# HDMI.net
KiCad netlist of a schematic drawn in Altium Designer
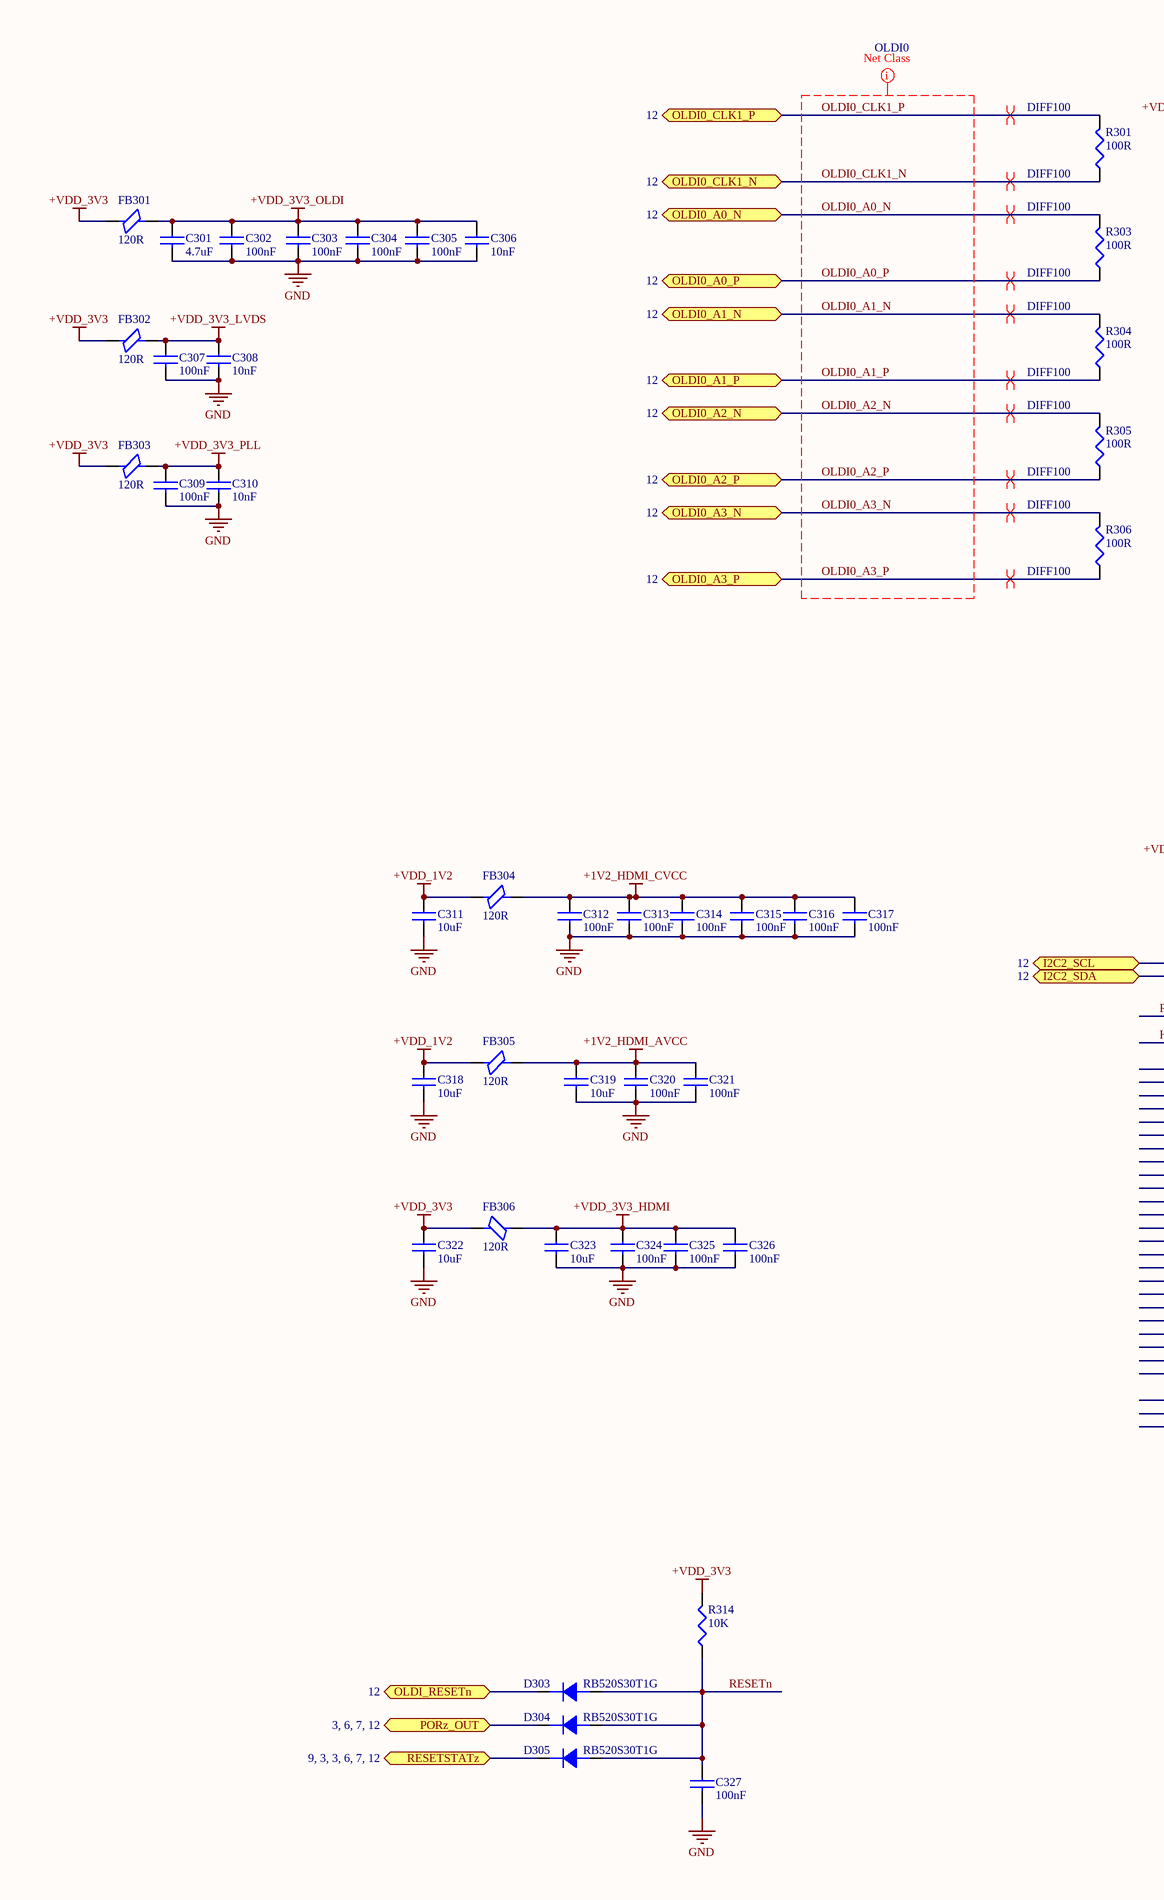
[diagram p0: HDMI.SchDoc, left]
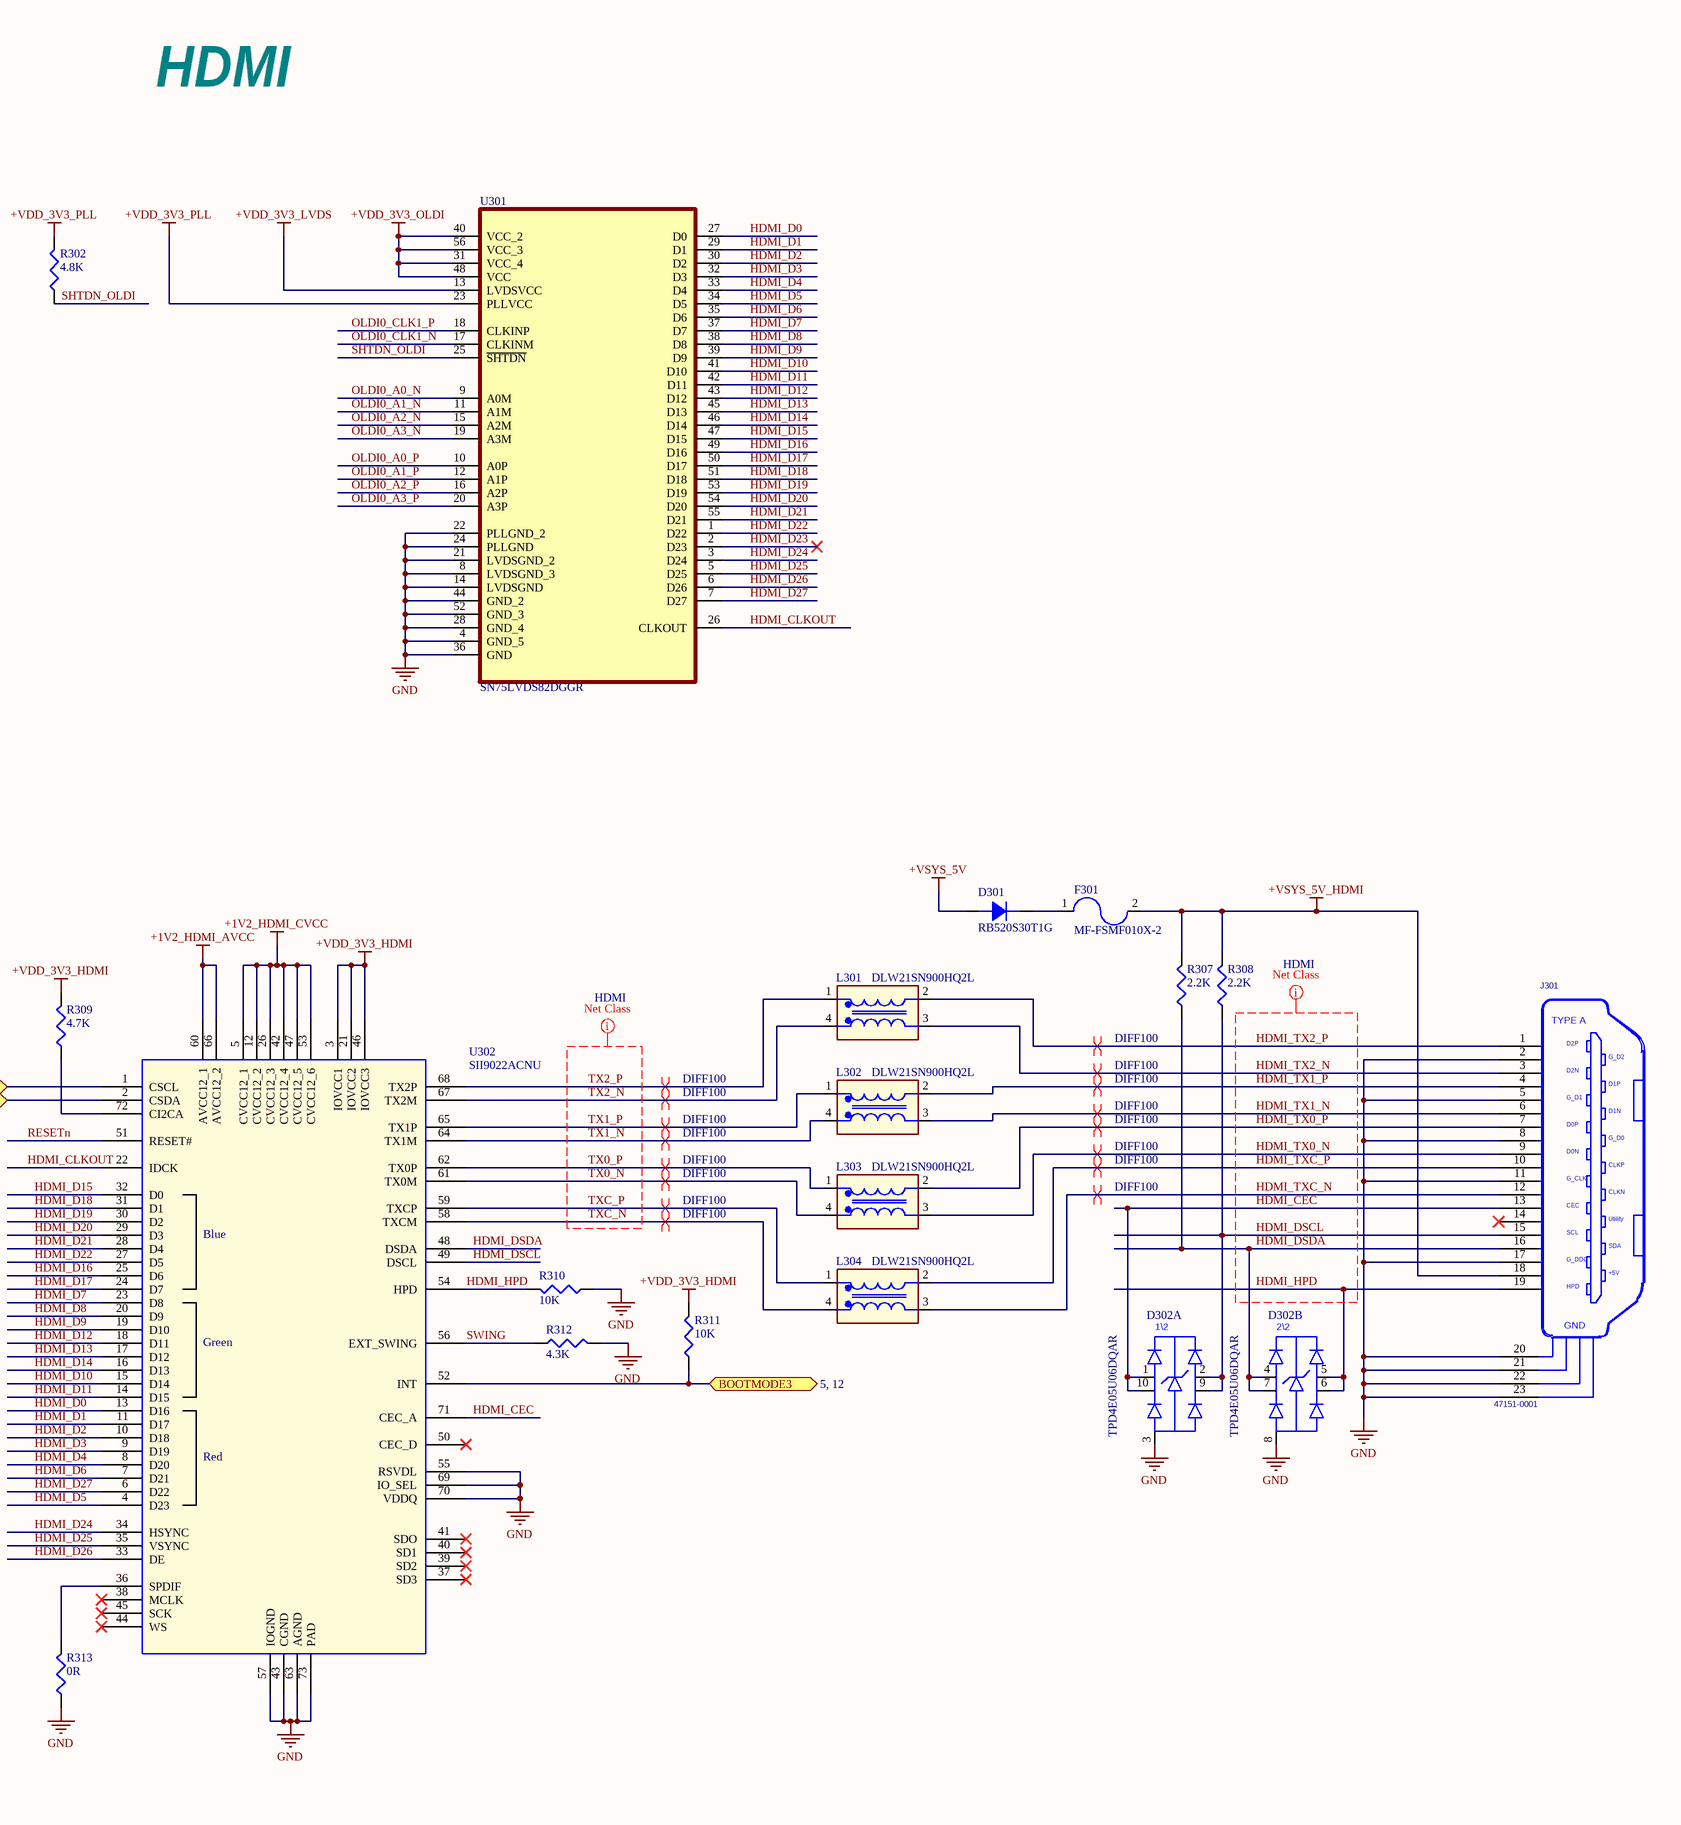
[diagram p1: HDMI.SchDoc, right]

(export (version "E")
  (design (tool "Eeschema 10.0.6"))
  (components
    (comp (ref "C301")
      (value "4.7uF")
      (footprint "C0402")
      (description "Multilayer Ceramic Capacitor, 4.7 uF, 6.3V, ± 10%, X5R, 0402 [1005 Metric]")
      (fields
        (field (name "MANUFACTURER") "Yageo")
        (field (name "MANUFACTURER PART NUMBER") "CC0402MRX5R5BB475")
      )
      (libsource (lib "Schlib SOM AM625") (part "CC0402MRX5R5BB475"))
    )
    (comp (ref "C302")
      (value "100nF")
      (footprint "C0603")
      (description "Multilayer Ceramic Capacitor, 0.1 uF, 25 V, ± 10%, X7R, 0603 [1608 Metric]")
      (fields
        (field (name "MANUFACTURER") "TDK")
        (field (name "MANUFACTURER PART NUMBER") "C1608X7R1E104K080AA")
      )
      (libsource (lib "Schlib SOM AM625") (part "C1608X7R1E104K080AA"))
    )
    (comp (ref "C303")
      (value "100nF")
      (footprint "C0603")
      (description "Multilayer Ceramic Capacitor, 0.1 uF, 25 V, ± 10%, X7R, 0603 [1608 Metric]")
      (fields
        (field (name "MANUFACTURER") "TDK")
        (field (name "MANUFACTURER PART NUMBER") "C1608X7R1E104K080AA")
      )
      (libsource (lib "Schlib SOM AM625") (part "C1608X7R1E104K080AA"))
    )
    (comp (ref "C304")
      (value "100nF")
      (footprint "C0603")
      (description "Multilayer Ceramic Capacitor, 0.1 uF, 25 V, ± 10%, X7R, 0603 [1608 Metric]")
      (fields
        (field (name "MANUFACTURER") "TDK")
        (field (name "MANUFACTURER PART NUMBER") "C1608X7R1E104K080AA")
      )
      (libsource (lib "Schlib SOM AM625") (part "C1608X7R1E104K080AA"))
    )
    (comp (ref "C305")
      (value "100nF")
      (footprint "C0603")
      (description "Multilayer Ceramic Capacitor, 0.1 uF, 25 V, ± 10%, X7R, 0603 [1608 Metric]")
      (fields
        (field (name "MANUFACTURER") "TDK")
        (field (name "MANUFACTURER PART NUMBER") "C1608X7R1E104K080AA")
      )
      (libsource (lib "Schlib SOM AM625") (part "C1608X7R1E104K080AA"))
    )
    (comp (ref "C306")
      (value "10nF")
      (footprint "C0402")
      (description "ESD SMD Comm X7R 0402 (1005Metric) ceramic capacitor 0.039Lx0.020W 1.00mmx0.50mm X7R ±10% 10000pF")
      (fields
        (field (name "MANUFACTURER") "KEMET")
        (field (name "MANUFACTURER PART NUMBER") "C0402C103K4REC7411")
      )
      (libsource (lib "Schlib SOM AM625") (part "C0402C103K4REC7411"))
    )
    (comp (ref "C307")
      (value "100nF")
      (footprint "C0603")
      (description "Multilayer Ceramic Capacitor, 0.1 uF, 25 V, ± 10%, X7R, 0603 [1608 Metric]")
      (fields
        (field (name "MANUFACTURER") "TDK")
        (field (name "MANUFACTURER PART NUMBER") "C1608X7R1E104K080AA")
      )
      (libsource (lib "Schlib SOM AM625") (part "C1608X7R1E104K080AA"))
    )
    (comp (ref "C308")
      (value "10nF")
      (footprint "C0402")
      (description "ESD SMD Comm X7R 0402 (1005Metric) ceramic capacitor 0.039Lx0.020W 1.00mmx0.50mm X7R ±10% 10000pF")
      (fields
        (field (name "MANUFACTURER") "KEMET")
        (field (name "MANUFACTURER PART NUMBER") "C0402C103K4REC7411")
      )
      (libsource (lib "Schlib SOM AM625") (part "C0402C103K4REC7411"))
    )
    (comp (ref "C309")
      (value "100nF")
      (footprint "C0603")
      (description "Multilayer Ceramic Capacitor, 0.1 uF, 25 V, ± 10%, X7R, 0603 [1608 Metric]")
      (fields
        (field (name "MANUFACTURER") "TDK")
        (field (name "MANUFACTURER PART NUMBER") "C1608X7R1E104K080AA")
      )
      (libsource (lib "Schlib SOM AM625") (part "C1608X7R1E104K080AA"))
    )
    (comp (ref "C310")
      (value "10nF")
      (footprint "C0402")
      (description "ESD SMD Comm X7R 0402 (1005Metric) ceramic capacitor 0.039Lx0.020W 1.00mmx0.50mm X7R ±10% 10000pF")
      (fields
        (field (name "MANUFACTURER") "KEMET")
        (field (name "MANUFACTURER PART NUMBER") "C0402C103K4REC7411")
      )
      (libsource (lib "Schlib SOM AM625") (part "C0402C103K4REC7411"))
    )
    (comp (ref "C311")
      (value "10uF")
      (footprint "C0603")
      (description "Multilayer Ceramic Capacitor, 10 uF, 10 V, ± 10%, X5R, 0603 [1608 Metric]")
      (fields
        (field (name "MANUFACTURER") "TDK")
        (field (name "MANUFACTURER PART NUMBER") "C1608X5R1A106K080AC")
      )
      (libsource (lib "Schlib SOM AM625") (part "C1608X5R1A106K080AC"))
    )
    (comp (ref "C312")
      (value "100nF")
      (footprint "C0201")
      (description "Multilayer Ceramic Capacitor, 0.1 uF, 16 V, ± 10%, X5R, 0201 [0603 Metric]")
      (fields
        (field (name "MANUFACTURER") "Yageo")
        (field (name "MANUFACTURER PART NUMBER") "CC0201KRX5R6BB104")
      )
      (libsource (lib "Schlib SOM AM625") (part "CC0201KRX5R6BB104"))
    )
    (comp (ref "C313")
      (value "100nF")
      (footprint "C0201")
      (description "Multilayer Ceramic Capacitor, 0.1 uF, 16 V, ± 10%, X5R, 0201 [0603 Metric]")
      (fields
        (field (name "MANUFACTURER") "Yageo")
        (field (name "MANUFACTURER PART NUMBER") "CC0201KRX5R6BB104")
      )
      (libsource (lib "Schlib SOM AM625") (part "CC0201KRX5R6BB104"))
    )
    (comp (ref "C314")
      (value "100nF")
      (footprint "C0201")
      (description "Multilayer Ceramic Capacitor, 0.1 uF, 16 V, ± 10%, X5R, 0201 [0603 Metric]")
      (fields
        (field (name "MANUFACTURER") "Yageo")
        (field (name "MANUFACTURER PART NUMBER") "CC0201KRX5R6BB104")
      )
      (libsource (lib "Schlib SOM AM625") (part "CC0201KRX5R6BB104"))
    )
    (comp (ref "C315")
      (value "100nF")
      (footprint "C0201")
      (description "Multilayer Ceramic Capacitor, 0.1 uF, 16 V, ± 10%, X5R, 0201 [0603 Metric]")
      (fields
        (field (name "MANUFACTURER") "Yageo")
        (field (name "MANUFACTURER PART NUMBER") "CC0201KRX5R6BB104")
      )
      (libsource (lib "Schlib SOM AM625") (part "CC0201KRX5R6BB104"))
    )
    (comp (ref "C316")
      (value "100nF")
      (footprint "C0201")
      (description "Multilayer Ceramic Capacitor, 0.1 uF, 16 V, ± 10%, X5R, 0201 [0603 Metric]")
      (fields
        (field (name "MANUFACTURER") "Yageo")
        (field (name "MANUFACTURER PART NUMBER") "CC0201KRX5R6BB104")
      )
      (libsource (lib "Schlib SOM AM625") (part "CC0201KRX5R6BB104"))
    )
    (comp (ref "C317")
      (value "100nF")
      (footprint "C0201")
      (description "Multilayer Ceramic Capacitor, 0.1 uF, 16 V, ± 10%, X5R, 0201 [0603 Metric]")
      (fields
        (field (name "MANUFACTURER") "Yageo")
        (field (name "MANUFACTURER PART NUMBER") "CC0201KRX5R6BB104")
      )
      (libsource (lib "Schlib SOM AM625") (part "CC0201KRX5R6BB104"))
    )
    (comp (ref "C318")
      (value "10uF")
      (footprint "C0603")
      (description "Multilayer Ceramic Capacitor, 10 uF, 10 V, ± 10%, X5R, 0603 [1608 Metric]")
      (fields
        (field (name "MANUFACTURER") "TDK")
        (field (name "MANUFACTURER PART NUMBER") "C1608X5R1A106K080AC")
      )
      (libsource (lib "Schlib SOM AM625") (part "C1608X5R1A106K080AC"))
    )
    (comp (ref "C319")
      (value "10uF")
      (footprint "C0603")
      (description "Multilayer Ceramic Capacitor, 10 uF, 10 V, ± 10%, X5R, 0603 [1608 Metric]")
      (fields
        (field (name "MANUFACTURER") "TDK")
        (field (name "MANUFACTURER PART NUMBER") "C1608X5R1A106K080AC")
      )
      (libsource (lib "Schlib SOM AM625") (part "C1608X5R1A106K080AC"))
    )
    (comp (ref "C320")
      (value "100nF")
      (footprint "C0201")
      (description "Multilayer Ceramic Capacitor, 0.1 uF, 16 V, ± 10%, X5R, 0201 [0603 Metric]")
      (fields
        (field (name "MANUFACTURER") "Yageo")
        (field (name "MANUFACTURER PART NUMBER") "CC0201KRX5R6BB104")
      )
      (libsource (lib "Schlib SOM AM625") (part "CC0201KRX5R6BB104"))
    )
    (comp (ref "C321")
      (value "100nF")
      (footprint "C0201")
      (description "Multilayer Ceramic Capacitor, 0.1 uF, 16 V, ± 10%, X5R, 0201 [0603 Metric]")
      (fields
        (field (name "MANUFACTURER") "Yageo")
        (field (name "MANUFACTURER PART NUMBER") "CC0201KRX5R6BB104")
      )
      (libsource (lib "Schlib SOM AM625") (part "CC0201KRX5R6BB104"))
    )
    (comp (ref "C322")
      (value "10uF")
      (footprint "C0603")
      (description "Multilayer Ceramic Capacitor, 10 uF, 10 V, ± 10%, X5R, 0603 [1608 Metric]")
      (fields
        (field (name "MANUFACTURER") "TDK")
        (field (name "MANUFACTURER PART NUMBER") "C1608X5R1A106K080AC")
      )
      (libsource (lib "Schlib SOM AM625") (part "C1608X5R1A106K080AC"))
    )
    (comp (ref "C323")
      (value "10uF")
      (footprint "C0603")
      (description "Multilayer Ceramic Capacitor, 10 uF, 10 V, ± 10%, X5R, 0603 [1608 Metric]")
      (fields
        (field (name "MANUFACTURER") "TDK")
        (field (name "MANUFACTURER PART NUMBER") "C1608X5R1A106K080AC")
      )
      (libsource (lib "Schlib SOM AM625") (part "C1608X5R1A106K080AC"))
    )
    (comp (ref "C324")
      (value "100nF")
      (footprint "C0201")
      (description "Multilayer Ceramic Capacitor, 0.1 uF, 16 V, ± 10%, X5R, 0201 [0603 Metric]")
      (fields
        (field (name "MANUFACTURER") "Yageo")
        (field (name "MANUFACTURER PART NUMBER") "CC0201KRX5R6BB104")
      )
      (libsource (lib "Schlib SOM AM625") (part "CC0201KRX5R6BB104"))
    )
    (comp (ref "C325")
      (value "100nF")
      (footprint "C0201")
      (description "Multilayer Ceramic Capacitor, 0.1 uF, 16 V, ± 10%, X5R, 0201 [0603 Metric]")
      (fields
        (field (name "MANUFACTURER") "Yageo")
        (field (name "MANUFACTURER PART NUMBER") "CC0201KRX5R6BB104")
      )
      (libsource (lib "Schlib SOM AM625") (part "CC0201KRX5R6BB104"))
    )
    (comp (ref "C326")
      (value "100nF")
      (footprint "C0201")
      (description "Multilayer Ceramic Capacitor, 0.1 uF, 16 V, ± 10%, X5R, 0201 [0603 Metric]")
      (fields
        (field (name "MANUFACTURER") "Yageo")
        (field (name "MANUFACTURER PART NUMBER") "CC0201KRX5R6BB104")
      )
      (libsource (lib "Schlib SOM AM625") (part "CC0201KRX5R6BB104"))
    )
    (comp (ref "C327")
      (value "100nF")
      (footprint "C0201")
      (description "Multilayer Ceramic Capacitor, 0.1 uF, 16 V, ± 10%, X5R, 0201 [0603 Metric]")
      (fields
        (field (name "MANUFACTURER") "Yageo")
        (field (name "MANUFACTURER PART NUMBER") "CC0201KRX5R6BB104")
      )
      (libsource (lib "Schlib SOM AM625") (part "CC0201KRX5R6BB104"))
    )
    (comp (ref "D301")
      (value "RB520S30T1G")
      (footprint "sod_523")
      (description "Diode Schottky 30V 0.2A 2-Pin SOD-523 T/R - Product that comes on tape, but is not reeled")
      (fields (field (name "MANUFACTURER") "ON Semiconductor"))
      (libsource (lib "Schlib SOM AM625") (part "RB520S30T1G"))
    )
    (comp (ref "D302")
      (value "TPD4E05U06DQAR")
      (footprint "10-USON")
      (description "Quad 0.5-pF, 5.5-V, ±12-kV ESD protection diode for USB, HDMI & High Speed Interfaces")
      (fields (field (name "MANUFACTURER") "Texas Instruments"))
      (libsource (lib "Schlib SOM AM625") (part "TPD4E05U06DQAR"))
    )
    (comp (ref "D303")
      (value "RB520S30T1G")
      (footprint "sod_523")
      (description "Diode Schottky 30V 0.2A 2-Pin SOD-523 T/R - Product that comes on tape, but is not reeled")
      (fields (field (name "MANUFACTURER") "ON Semiconductor"))
      (libsource (lib "Schlib SOM AM625") (part "RB520S30T1G"))
    )
    (comp (ref "D304")
      (value "RB520S30T1G")
      (footprint "sod_523")
      (description "Diode Schottky 30V 0.2A 2-Pin SOD-523 T/R - Product that comes on tape, but is not reeled")
      (fields (field (name "MANUFACTURER") "ON Semiconductor"))
      (libsource (lib "Schlib SOM AM625") (part "RB520S30T1G"))
    )
    (comp (ref "D305")
      (value "RB520S30T1G")
      (footprint "sod_523")
      (description "Diode Schottky 30V 0.2A 2-Pin SOD-523 T/R - Product that comes on tape, but is not reeled")
      (fields (field (name "MANUFACTURER") "ON Semiconductor"))
      (libsource (lib "Schlib SOM AM625") (part "RB520S30T1G"))
    )
    (comp (ref "F301")
      (value "MF-FSMF010X-2")
      (footprint "f0603")
      (fields (field (name "MANUFACTURER") "Bourns"))
      (libsource (lib "Schlib SOM AM625") (part "MF-FSMF010X-2"))
    )
    (comp (ref "FB301")
      (value "120R")
      (footprint "FB0402")
      (description "Ferrite Beads Multi-Layer 120Ohm 25% 100MHz 1.3A 0.09Ohm DCR 0402 Automotive T/R")
      (fields
        (field (name "MANUFACTURER") "Murata")
        (field (name "MANUFACTURER PART NUMBER") "BLM15PD121SZ1D")
      )
      (libsource (lib "Schlib SOM AM625") (part "BLM15PD121SZ1D"))
    )
    (comp (ref "FB302")
      (value "120R")
      (footprint "FB0402")
      (description "Ferrite Beads Multi-Layer 120Ohm 25% 100MHz 1.3A 0.09Ohm DCR 0402 Automotive T/R")
      (fields
        (field (name "MANUFACTURER") "Murata")
        (field (name "MANUFACTURER PART NUMBER") "BLM15PD121SZ1D")
      )
      (libsource (lib "Schlib SOM AM625") (part "BLM15PD121SZ1D"))
    )
    (comp (ref "FB303")
      (value "120R")
      (footprint "FB0402")
      (description "Ferrite Beads Multi-Layer 120Ohm 25% 100MHz 1.3A 0.09Ohm DCR 0402 Automotive T/R")
      (fields
        (field (name "MANUFACTURER") "Murata")
        (field (name "MANUFACTURER PART NUMBER") "BLM15PD121SZ1D")
      )
      (libsource (lib "Schlib SOM AM625") (part "BLM15PD121SZ1D"))
    )
    (comp (ref "FB304")
      (value "120R")
      (footprint "FB0402")
      (description "Ferrite Beads Multi-Layer 120Ohm 25% 100MHz 1.3A 0.09Ohm DCR 0402 Automotive T/R")
      (fields
        (field (name "MANUFACTURER") "Murata")
        (field (name "MANUFACTURER PART NUMBER") "BLM15PD121SZ1D")
      )
      (libsource (lib "Schlib SOM AM625") (part "BLM15PD121SZ1D"))
    )
    (comp (ref "FB305")
      (value "120R")
      (footprint "FB0402")
      (description "Ferrite Beads Multi-Layer 120Ohm 25% 100MHz 1.3A 0.09Ohm DCR 0402 Automotive T/R")
      (fields
        (field (name "MANUFACTURER") "Murata")
        (field (name "MANUFACTURER PART NUMBER") "BLM15PD121SZ1D")
      )
      (libsource (lib "Schlib SOM AM625") (part "BLM15PD121SZ1D"))
    )
    (comp (ref "FB306")
      (value "120R")
      (footprint "FB0402")
      (description "Ferrite Beads Multi-Layer 120Ohm 25% 100MHz 1.3A 0.09Ohm DCR 0402 Automotive T/R")
      (fields
        (field (name "MANUFACTURER") "Murata")
        (field (name "MANUFACTURER PART NUMBER") "BLM15PD121SZ1D")
      )
      (libsource (lib "Schlib SOM AM625") (part "BLM15PD121SZ1D"))
    )
    (comp (ref "J301")
      (value "47151-0001")
      (footprint "HDMI")
      (description "CONN RCPT 19POS HDMI RT ANG SMD")
      (fields (field (name "MANUFACTURER") "Molex Connector Corporation"))
      (libsource (lib "Schlib SOM AM625") (part "47151-0001"))
    )
    (comp (ref "L301")
      (value "DLW21SN900HQ2L")
      (footprint "IND_DLW21S_0805_MUR")
      (description "Ind Common Mode Choke Wirewound 90Ohm 25% 100MHz 280mA 0805 Embossed T/R")
      (fields (field (name "MANUFACTURER") "Murata") (field (name "TOLERANCE") "25%"))
      (libsource (lib "Schlib SOM AM625") (part "DLW21SN900HQ2L"))
    )
    (comp (ref "L302")
      (value "DLW21SN900HQ2L")
      (footprint "IND_DLW21S_0805_MUR")
      (description "Ind Common Mode Choke Wirewound 90Ohm 25% 100MHz 280mA 0805 Embossed T/R")
      (fields (field (name "MANUFACTURER") "Murata") (field (name "TOLERANCE") "25%"))
      (libsource (lib "Schlib SOM AM625") (part "DLW21SN900HQ2L"))
    )
    (comp (ref "L303")
      (value "DLW21SN900HQ2L")
      (footprint "IND_DLW21S_0805_MUR")
      (description "Ind Common Mode Choke Wirewound 90Ohm 25% 100MHz 280mA 0805 Embossed T/R")
      (fields (field (name "MANUFACTURER") "Murata") (field (name "TOLERANCE") "25%"))
      (libsource (lib "Schlib SOM AM625") (part "DLW21SN900HQ2L"))
    )
    (comp (ref "L304")
      (value "DLW21SN900HQ2L")
      (footprint "IND_DLW21S_0805_MUR")
      (description "Ind Common Mode Choke Wirewound 90Ohm 25% 100MHz 280mA 0805 Embossed T/R")
      (fields (field (name "MANUFACTURER") "Murata") (field (name "TOLERANCE") "25%"))
      (libsource (lib "Schlib SOM AM625") (part "DLW21SN900HQ2L"))
    )
    (comp (ref "R301")
      (value "100R")
      (footprint "R0402")
      (description "SMD Chip Resistor, 100 Ohm, ± 1%, 63 mW, 0402 [1005 Metric], Thick Film, General Purpose")
      (fields
        (field (name "MANUFACTURER") "Yageo")
        (field (name "MANUFACTURER PART NUMBER") "RC0402FR-07100RL")
      )
      (libsource (lib "Schlib SOM AM625") (part "RC0402FR-07100RL"))
    )
    (comp (ref "R302")
      (value "4.8K")
      (footprint "R0402")
      (description "Res SMD 4.8K Ohm 1% 1/10W 0603")
      (fields
        (field (name "MANUFACTURER") "VPG Foil Resistors")
        (field (name "MANUFACTURER PART NUMBER") "Y16364K80000F9R")
      )
      (libsource (lib "Schlib SOM AM625") (part "Y16364K80000F9R"))
    )
    (comp (ref "R303")
      (value "100R")
      (footprint "R0402")
      (description "SMD Chip Resistor, 100 Ohm, ± 1%, 63 mW, 0402 [1005 Metric], Thick Film, General Purpose")
      (fields
        (field (name "MANUFACTURER") "Yageo")
        (field (name "MANUFACTURER PART NUMBER") "RC0402FR-07100RL")
      )
      (libsource (lib "Schlib SOM AM625") (part "RC0402FR-07100RL"))
    )
    (comp (ref "R304")
      (value "100R")
      (footprint "R0402")
      (description "SMD Chip Resistor, 100 Ohm, ± 1%, 63 mW, 0402 [1005 Metric], Thick Film, General Purpose")
      (fields
        (field (name "MANUFACTURER") "Yageo")
        (field (name "MANUFACTURER PART NUMBER") "RC0402FR-07100RL")
      )
      (libsource (lib "Schlib SOM AM625") (part "RC0402FR-07100RL"))
    )
    (comp (ref "R305")
      (value "100R")
      (footprint "R0402")
      (description "SMD Chip Resistor, 100 Ohm, ± 1%, 63 mW, 0402 [1005 Metric], Thick Film, General Purpose")
      (fields
        (field (name "MANUFACTURER") "Yageo")
        (field (name "MANUFACTURER PART NUMBER") "RC0402FR-07100RL")
      )
      (libsource (lib "Schlib SOM AM625") (part "RC0402FR-07100RL"))
    )
    (comp (ref "R306")
      (value "100R")
      (footprint "R0402")
      (description "SMD Chip Resistor, 100 Ohm, ± 1%, 63 mW, 0402 [1005 Metric], Thick Film, General Purpose")
      (fields
        (field (name "MANUFACTURER") "Yageo")
        (field (name "MANUFACTURER PART NUMBER") "RC0402FR-07100RL")
      )
      (libsource (lib "Schlib SOM AM625") (part "RC0402FR-07100RL"))
    )
    (comp (ref "R307")
      (value "2.2K")
      (footprint "R0201")
      (description "SMD Chip Resistor, 2.2 kOhm, ± 1%, 50 mW, 0201 [0603 Metric], Thick Film, General Purpose")
      (fields
        (field (name "MANUFACTURER") "Yageo")
        (field (name "MANUFACTURER PART NUMBER") "RC0201FR-072K2L")
      )
      (libsource (lib "Schlib SOM AM625") (part "RC0201FR-072K2L"))
    )
    (comp (ref "R308")
      (value "2.2K")
      (footprint "R0201")
      (description "SMD Chip Resistor, 2.2 kOhm, ± 1%, 50 mW, 0201 [0603 Metric], Thick Film, General Purpose")
      (fields
        (field (name "MANUFACTURER") "Yageo")
        (field (name "MANUFACTURER PART NUMBER") "RC0201FR-072K2L")
      )
      (libsource (lib "Schlib SOM AM625") (part "RC0201FR-072K2L"))
    )
    (comp (ref "R309")
      (value "4.7K")
      (footprint "R0402")
      (description "SMD Chip Resistor, 4.7 kOhm, ± 1%, 63 mW, 0402 [1005 Metric], Thick Film, General Purpose")
      (fields
        (field (name "MANUFACTURER") "Yageo")
        (field (name "MANUFACTURER PART NUMBER") "RC0402FR-074K7L")
      )
      (libsource (lib "Schlib SOM AM625") (part "RC0402FR-074K7L"))
    )
    (comp (ref "R310")
      (value "10K")
      (footprint "R0201")
      (description "Res Thick Film 0201 10K Ohm 5% 1/20W ±200ppm/°C Molded SMD SMD Paper T/R")
      (fields
        (field (name "MANUFACTURER") "Yageo")
        (field (name "MANUFACTURER PART NUMBER") "RC0201JR-0710KL")
      )
      (libsource (lib "Schlib SOM AM625") (part "RC0201JR-0710KL"))
    )
    (comp (ref "R311")
      (value "10K")
      (footprint "R0201")
      (description "Res Thick Film 0201 10K Ohm 5% 1/20W ±200ppm/°C Molded SMD SMD Paper T/R")
      (fields
        (field (name "MANUFACTURER") "Yageo")
        (field (name "MANUFACTURER PART NUMBER") "RC0201JR-0710KL")
      )
      (libsource (lib "Schlib SOM AM625") (part "RC0201JR-0710KL"))
    )
    (comp (ref "R312")
      (value "4.3K")
      (footprint "R0402")
      (description "SMD Chip Resistor, 4.3 kOhm, ± 1%, 63 mW, 0402 [1005 Metric], Thick Film, General Purpose")
      (fields
        (field (name "MANUFACTURER") "Yageo")
        (field (name "MANUFACTURER PART NUMBER") "RC0402FR-074K3L")
      )
      (libsource (lib "Schlib SOM AM625") (part "RC0402FR-074K3L"))
    )
    (comp (ref "R313")
      (value "0R")
      (footprint "R0201")
      (description "Zero Ohm Resistor, Jumper, 0201 [0603 Metric], Thick Film, 50 mW, 500 mA, Surface Mount")
      (fields
        (field (name "MANUFACTURER") "Yageo")
        (field (name "MANUFACTURER PART NUMBER") "RC0201JR-070RL")
      )
      (libsource (lib "Schlib SOM AM625") (part "RC0201JR-070RL"))
    )
    (comp (ref "R314")
      (value "10K")
      (footprint "R0402")
      (description "RES 10.0K OHM 1/16W 1% 0402 SMD")
      (fields
        (field (name "MANUFACTURER") "Yageo")
        (field (name "MANUFACTURER PART NUMBER") "RC0402FR-0710KL")
      )
      (libsource (lib "Schlib SOM AM625") (part "RC0402FR-0710KL"))
    )
    (comp (ref "U301")
      (value "SN75LVDS82DGGR")
      (footprint "SOP50P810X120-56N")
      (description "0/5 Receiver  LVDS 56-TSSOP")
      (fields (field (name "MANUFACTURER") "Texas Instruments"))
      (libsource (lib "Schlib SOM AM625") (part "SN75LVDS82DGGR"))
    )
    (comp (ref "U302")
      (value "SII9022ACNU")
      (footprint "QFN50P1000X1000X90-73N")
      (description "24-Bit RGB Input HDMI 1.4a Transmitter, 1080p@60Hz, no HDCP, 72-pin QFN")
      (fields (field (name "MANUFACTURER") "Lattice Semiconductor"))
      (libsource (lib "Schlib SOM AM625") (part "SII9022ACNU"))
    )
  )
  (nets
    (net (code "1") (name "+1V2_HDMI_AVCC") (class "Default")
      (node (ref "C319") (pin "1") (pinfunction "1_1") (pintype "passive"))
      (node (ref "C320") (pin "1") (pinfunction "1_1") (pintype "passive"))
      (node (ref "C321") (pin "1") (pinfunction "1_1") (pintype "passive"))
      (node (ref "FB305") (pin "2") (pinfunction "2_2") (pintype "passive"))
      (node (ref "U302") (pin "60") (pinfunction "AVCC12_1_60") (pintype "passive"))
      (node (ref "U302") (pin "66") (pinfunction "AVCC12_2_66") (pintype "passive"))
    )
    (net (code "2") (name "+1V2_HDMI_CVCC") (class "Default")
      (node (ref "C312") (pin "1") (pinfunction "1_1") (pintype "passive"))
      (node (ref "C313") (pin "1") (pinfunction "1_1") (pintype "passive"))
      (node (ref "C314") (pin "1") (pinfunction "1_1") (pintype "passive"))
      (node (ref "C315") (pin "1") (pinfunction "1_1") (pintype "passive"))
      (node (ref "C316") (pin "1") (pinfunction "1_1") (pintype "passive"))
      (node (ref "C317") (pin "1") (pinfunction "1_1") (pintype "passive"))
      (node (ref "FB304") (pin "2") (pinfunction "2_2") (pintype "passive"))
      (node (ref "U302") (pin "12") (pinfunction "CVCC12_2_12") (pintype "passive"))
      (node (ref "U302") (pin "26") (pinfunction "CVCC12_3_26") (pintype "passive"))
      (node (ref "U302") (pin "42") (pinfunction "CVCC12_4_42") (pintype "passive"))
      (node (ref "U302") (pin "47") (pinfunction "CVCC12_5_47") (pintype "passive"))
      (node (ref "U302") (pin "5") (pinfunction "CVCC12_1_5") (pintype "passive"))
      (node (ref "U302") (pin "53") (pinfunction "CVCC12_6_53") (pintype "passive"))
    )
    (net (code "3") (name "+VDD_1V2") (class "Default")
      (node (ref "C311") (pin "1") (pinfunction "1_1") (pintype "passive"))
      (node (ref "C318") (pin "1") (pinfunction "1_1") (pintype "passive"))
      (node (ref "FB304") (pin "1") (pinfunction "1_1") (pintype "passive"))
      (node (ref "FB305") (pin "1") (pinfunction "1_1") (pintype "passive"))
    )
    (net (code "4") (name "+VDD_3V3") (class "Default")
      (node (ref "C322") (pin "1") (pinfunction "1_1") (pintype "passive"))
      (node (ref "FB301") (pin "1") (pinfunction "1_1") (pintype "passive"))
      (node (ref "FB302") (pin "1") (pinfunction "1_1") (pintype "passive"))
      (node (ref "FB303") (pin "1") (pinfunction "1_1") (pintype "passive"))
      (node (ref "FB306") (pin "2") (pinfunction "2_2") (pintype "passive"))
      (node (ref "R314") (pin "2") (pinfunction "2_2") (pintype "passive"))
    )
    (net (code "5") (name "+VDD_3V3_HDMI") (class "Default")
      (node (ref "C323") (pin "1") (pinfunction "1_1") (pintype "passive"))
      (node (ref "C324") (pin "1") (pinfunction "1_1") (pintype "passive"))
      (node (ref "C325") (pin "1") (pinfunction "1_1") (pintype "passive"))
      (node (ref "C326") (pin "1") (pinfunction "1_1") (pintype "passive"))
      (node (ref "FB306") (pin "1") (pinfunction "1_1") (pintype "passive"))
      (node (ref "R309") (pin "2") (pinfunction "2_2") (pintype "passive"))
      (node (ref "R311") (pin "2") (pinfunction "2_2") (pintype "passive"))
      (node (ref "U302") (pin "21") (pinfunction "IOVCC2_21") (pintype "passive"))
      (node (ref "U302") (pin "3") (pinfunction "IOVCC1_3") (pintype "passive"))
      (node (ref "U302") (pin "46") (pinfunction "IOVCC3_46") (pintype "passive"))
    )
    (net (code "6") (name "+VDD_3V3_LVDS") (class "Default")
      (node (ref "C307") (pin "1") (pinfunction "1_1") (pintype "passive"))
      (node (ref "C308") (pin "1") (pinfunction "1_1") (pintype "passive"))
      (node (ref "FB302") (pin "2") (pinfunction "2_2") (pintype "passive"))
      (node (ref "U301") (pin "13") (pinfunction "LVDSVCC_13") (pintype "passive"))
    )
    (net (code "7") (name "+VDD_3V3_OLDI") (class "Default")
      (node (ref "C301") (pin "1") (pinfunction "1_1") (pintype "passive"))
      (node (ref "C302") (pin "1") (pinfunction "1_1") (pintype "passive"))
      (node (ref "C303") (pin "1") (pinfunction "1_1") (pintype "passive"))
      (node (ref "C304") (pin "1") (pinfunction "1_1") (pintype "passive"))
      (node (ref "C305") (pin "1") (pinfunction "1_1") (pintype "passive"))
      (node (ref "C306") (pin "1") (pinfunction "1_1") (pintype "passive"))
      (node (ref "FB301") (pin "2") (pinfunction "2_2") (pintype "passive"))
      (node (ref "U301") (pin "31") (pinfunction "VCC_4_31") (pintype "passive"))
      (node (ref "U301") (pin "40") (pinfunction "VCC_2_40") (pintype "passive"))
      (node (ref "U301") (pin "48") (pinfunction "VCC_48") (pintype "passive"))
      (node (ref "U301") (pin "56") (pinfunction "VCC_3_56") (pintype "passive"))
    )
    (net (code "8") (name "+VDD_3V3_PLL") (class "Default")
      (node (ref "C309") (pin "1") (pinfunction "1_1") (pintype "passive"))
      (node (ref "C310") (pin "1") (pinfunction "1_1") (pintype "passive"))
      (node (ref "FB303") (pin "2") (pinfunction "2_2") (pintype "passive"))
      (node (ref "R302") (pin "2") (pinfunction "2_2") (pintype "passive"))
      (node (ref "U301") (pin "23") (pinfunction "PLLVCC_23") (pintype "passive"))
    )
    (net (code "9") (name "+VSYS_5V") (class "Default")
      (node (ref "D301") (pin "1") (pinfunction "A_1") (pintype "passive"))
    )
    (net (code "10") (name "+VSYS_5V_HDMI") (class "Default")
      (node (ref "F301") (pin "2") (pinfunction "2_2") (pintype "passive"))
      (node (ref "J301") (pin "18") (pinfunction "+5V_18") (pintype "passive"))
      (node (ref "R307") (pin "2") (pinfunction "2_2") (pintype "passive"))
      (node (ref "R308") (pin "2") (pinfunction "2_2") (pintype "passive"))
    )
    (net (code "11") (name "/BOOTMODE3") (class "Default")
      (node (ref "R311") (pin "1") (pinfunction "1_1") (pintype "passive"))
      (node (ref "U302") (pin "52") (pinfunction "INT_52") (pintype "passive"))
    )
    (net (code "12") (name "/HDMI_CEC") (class "Default")
      (node (ref "D302") (pin "1") (pinfunction "1A_1") (pintype "passive"))
      (node (ref "D302") (pin "10") (pinfunction "1B_10") (pintype "passive"))
      (node (ref "J301") (pin "13") (pinfunction "CEC_13") (pintype "passive"))
      (node (ref "U302") (pin "71") (pinfunction "CEC_A_71") (pintype "passive"))
    )
    (net (code "13") (name "/HDMI_CLKOUT") (class "Default")
      (node (ref "U301") (pin "26") (pinfunction "CLKOUT_26") (pintype "passive"))
      (node (ref "U302") (pin "22") (pinfunction "IDCK_22") (pintype "passive"))
    )
    (net (code "14") (name "/HDMI_D0") (class "Default")
      (node (ref "U301") (pin "27") (pinfunction "D0_27") (pintype "passive"))
      (node (ref "U302") (pin "13") (pinfunction "D16_13") (pintype "passive"))
    )
    (net (code "15") (name "/HDMI_D1") (class "Default")
      (node (ref "U301") (pin "29") (pinfunction "D1_29") (pintype "passive"))
      (node (ref "U302") (pin "11") (pinfunction "D17_11") (pintype "passive"))
    )
    (net (code "16") (name "/HDMI_D2") (class "Default")
      (node (ref "U301") (pin "30") (pinfunction "D2_30") (pintype "passive"))
      (node (ref "U302") (pin "10") (pinfunction "D18_10") (pintype "passive"))
    )
    (net (code "17") (name "/HDMI_D3") (class "Default")
      (node (ref "U301") (pin "32") (pinfunction "D3_32") (pintype "passive"))
      (node (ref "U302") (pin "9") (pinfunction "D19_9") (pintype "passive"))
    )
    (net (code "18") (name "/HDMI_D4") (class "Default")
      (node (ref "U301") (pin "33") (pinfunction "D4_33") (pintype "passive"))
      (node (ref "U302") (pin "8") (pinfunction "D20_8") (pintype "passive"))
    )
    (net (code "19") (name "/HDMI_D5") (class "Default")
      (node (ref "U301") (pin "34") (pinfunction "D5_34") (pintype "passive"))
      (node (ref "U302") (pin "4") (pinfunction "D23_4") (pintype "passive"))
    )
    (net (code "20") (name "/HDMI_D6") (class "Default")
      (node (ref "U301") (pin "35") (pinfunction "D6_35") (pintype "passive"))
      (node (ref "U302") (pin "7") (pinfunction "D21_7") (pintype "passive"))
    )
    (net (code "21") (name "/HDMI_D7") (class "Default")
      (node (ref "U301") (pin "37") (pinfunction "D7_37") (pintype "passive"))
      (node (ref "U302") (pin "23") (pinfunction "D8_23") (pintype "passive"))
    )
    (net (code "22") (name "/HDMI_D8") (class "Default")
      (node (ref "U301") (pin "38") (pinfunction "D8_38") (pintype "passive"))
      (node (ref "U302") (pin "20") (pinfunction "D9_20") (pintype "passive"))
    )
    (net (code "23") (name "/HDMI_D9") (class "Default")
      (node (ref "U301") (pin "39") (pinfunction "D9_39") (pintype "passive"))
      (node (ref "U302") (pin "19") (pinfunction "D10_19") (pintype "passive"))
    )
    (net (code "24") (name "/HDMI_D10") (class "Default")
      (node (ref "U301") (pin "41") (pinfunction "D10_41") (pintype "passive"))
      (node (ref "U302") (pin "15") (pinfunction "D14_15") (pintype "passive"))
    )
    (net (code "25") (name "/HDMI_D11") (class "Default")
      (node (ref "U301") (pin "42") (pinfunction "D11_42") (pintype "passive"))
      (node (ref "U302") (pin "14") (pinfunction "D15_14") (pintype "passive"))
    )
    (net (code "26") (name "/HDMI_D12") (class "Default")
      (node (ref "U301") (pin "43") (pinfunction "D12_43") (pintype "passive"))
      (node (ref "U302") (pin "18") (pinfunction "D11_18") (pintype "passive"))
    )
    (net (code "27") (name "/HDMI_D13") (class "Default")
      (node (ref "U301") (pin "45") (pinfunction "D13_45") (pintype "passive"))
      (node (ref "U302") (pin "17") (pinfunction "D12_17") (pintype "passive"))
    )
    (net (code "28") (name "/HDMI_D14") (class "Default")
      (node (ref "U301") (pin "46") (pinfunction "D14_46") (pintype "passive"))
      (node (ref "U302") (pin "16") (pinfunction "D13_16") (pintype "passive"))
    )
    (net (code "29") (name "/HDMI_D15") (class "Default")
      (node (ref "U301") (pin "47") (pinfunction "D15_47") (pintype "passive"))
      (node (ref "U302") (pin "32") (pinfunction "D0_32") (pintype "passive"))
    )
    (net (code "30") (name "/HDMI_D16") (class "Default")
      (node (ref "U301") (pin "49") (pinfunction "D16_49") (pintype "passive"))
      (node (ref "U302") (pin "25") (pinfunction "D6_25") (pintype "passive"))
    )
    (net (code "31") (name "/HDMI_D17") (class "Default")
      (node (ref "U301") (pin "50") (pinfunction "D17_50") (pintype "passive"))
      (node (ref "U302") (pin "24") (pinfunction "D7_24") (pintype "passive"))
    )
    (net (code "32") (name "/HDMI_D18") (class "Default")
      (node (ref "U301") (pin "51") (pinfunction "D18_51") (pintype "passive"))
      (node (ref "U302") (pin "31") (pinfunction "D1_31") (pintype "passive"))
    )
    (net (code "33") (name "/HDMI_D19") (class "Default")
      (node (ref "U301") (pin "53") (pinfunction "D19_53") (pintype "passive"))
      (node (ref "U302") (pin "30") (pinfunction "D2_30") (pintype "passive"))
    )
    (net (code "34") (name "/HDMI_D20") (class "Default")
      (node (ref "U301") (pin "54") (pinfunction "D20_54") (pintype "passive"))
      (node (ref "U302") (pin "29") (pinfunction "D3_29") (pintype "passive"))
    )
    (net (code "35") (name "/HDMI_D21") (class "Default")
      (node (ref "U301") (pin "55") (pinfunction "D21_55") (pintype "passive"))
      (node (ref "U302") (pin "28") (pinfunction "D4_28") (pintype "passive"))
    )
    (net (code "36") (name "/HDMI_D22") (class "Default")
      (node (ref "U301") (pin "1") (pinfunction "D22_1") (pintype "passive"))
      (node (ref "U302") (pin "27") (pinfunction "D5_27") (pintype "passive"))
    )
    (net (code "37") (name "/HDMI_D23") (class "Default")
      (node (ref "U301") (pin "2") (pinfunction "D23_2") (pintype "passive+no_connect"))
    )
    (net (code "38") (name "/HDMI_D24") (class "Default")
      (node (ref "U301") (pin "3") (pinfunction "D24_3") (pintype "passive"))
      (node (ref "U302") (pin "34") (pinfunction "HSYNC_34") (pintype "passive"))
    )
    (net (code "39") (name "/HDMI_D25") (class "Default")
      (node (ref "U301") (pin "5") (pinfunction "D25_5") (pintype "passive"))
      (node (ref "U302") (pin "35") (pinfunction "VSYNC_35") (pintype "passive"))
    )
    (net (code "40") (name "/HDMI_D26") (class "Default")
      (node (ref "U301") (pin "6") (pinfunction "D26_6") (pintype "passive"))
      (node (ref "U302") (pin "33") (pinfunction "DE_33") (pintype "passive"))
    )
    (net (code "41") (name "/HDMI_D27") (class "Default")
      (node (ref "U301") (pin "7") (pinfunction "D27_7") (pintype "passive"))
      (node (ref "U302") (pin "6") (pinfunction "D22_6") (pintype "passive"))
    )
    (net (code "42") (name "/HDMI_DSCL") (class "Default")
      (node (ref "D302") (pin "2") (pinfunction "2A_2") (pintype "passive"))
      (node (ref "D302") (pin "9") (pinfunction "2B_9") (pintype "passive"))
      (node (ref "J301") (pin "15") (pinfunction "SCL_15") (pintype "passive"))
      (node (ref "R308") (pin "1") (pinfunction "1_1") (pintype "passive"))
      (node (ref "U302") (pin "49") (pinfunction "DSCL_49") (pintype "passive"))
    )
    (net (code "43") (name "/HDMI_DSDA") (class "Default")
      (node (ref "D302") (pin "4") (pinfunction "3A_4") (pintype "passive"))
      (node (ref "D302") (pin "7") (pinfunction "3B_7") (pintype "passive"))
      (node (ref "J301") (pin "16") (pinfunction "SDA_16") (pintype "passive"))
      (node (ref "R307") (pin "1") (pinfunction "1_1") (pintype "passive"))
      (node (ref "U302") (pin "48") (pinfunction "DSDA_48") (pintype "passive"))
    )
    (net (code "44") (name "/HDMI_HPD") (class "Default")
      (node (ref "D302") (pin "5") (pinfunction "4A_5") (pintype "passive"))
      (node (ref "D302") (pin "6") (pinfunction "4B_6") (pintype "passive"))
      (node (ref "J301") (pin "19") (pinfunction "HPD_19") (pintype "passive"))
      (node (ref "R310") (pin "2") (pinfunction "2_2") (pintype "passive"))
      (node (ref "U302") (pin "54") (pinfunction "HPD_54") (pintype "passive"))
    )
    (net (code "45") (name "/HDMI_TX0_N") (class "Default")
      (node (ref "J301") (pin "9") (pinfunction "D0-_9") (pintype "passive"))
      (node (ref "L303") (pin "3") (pinfunction "3_3") (pintype "passive"))
    )
    (net (code "46") (name "/HDMI_TX0_P") (class "Default")
      (node (ref "J301") (pin "7") (pinfunction "D0+_7") (pintype "passive"))
      (node (ref "L303") (pin "2") (pinfunction "2_2") (pintype "passive"))
    )
    (net (code "47") (name "/HDMI_TX1_N") (class "Default")
      (node (ref "J301") (pin "6") (pinfunction "D1-_6") (pintype "passive"))
      (node (ref "L302") (pin "3") (pinfunction "3_3") (pintype "passive"))
    )
    (net (code "48") (name "/HDMI_TX1_P") (class "Default")
      (node (ref "J301") (pin "4") (pinfunction "D1+_4") (pintype "passive"))
      (node (ref "L302") (pin "2") (pinfunction "2_2") (pintype "passive"))
    )
    (net (code "49") (name "/HDMI_TX2_N") (class "Default")
      (node (ref "J301") (pin "3") (pinfunction "D2-_3") (pintype "passive"))
      (node (ref "L301") (pin "3") (pinfunction "3_3") (pintype "passive"))
    )
    (net (code "50") (name "/HDMI_TX2_P") (class "Default")
      (node (ref "J301") (pin "1") (pinfunction "D2+_1") (pintype "passive"))
      (node (ref "L301") (pin "2") (pinfunction "2_2") (pintype "passive"))
    )
    (net (code "51") (name "/HDMI_TXC_N") (class "Default")
      (node (ref "J301") (pin "12") (pinfunction "CK-_12") (pintype "passive"))
      (node (ref "L304") (pin "3") (pinfunction "3_3") (pintype "passive"))
    )
    (net (code "52") (name "/HDMI_TXC_P") (class "Default")
      (node (ref "J301") (pin "10") (pinfunction "CK+_10") (pintype "passive"))
      (node (ref "L304") (pin "2") (pinfunction "2_2") (pintype "passive"))
    )
    (net (code "53") (name "/I2C2_SCL") (class "Default")
      (node (ref "U302") (pin "1") (pinfunction "CSCL_1") (pintype "passive"))
    )
    (net (code "54") (name "/I2C2_SDA") (class "Default")
      (node (ref "U302") (pin "2") (pinfunction "CSDA_2") (pintype "passive"))
    )
    (net (code "55") (name "/OLDI0_A0_N") (class "Default")
      (node (ref "R303") (pin "2") (pinfunction "2_2") (pintype "passive"))
      (node (ref "U301") (pin "9") (pinfunction "A0M_9") (pintype "passive"))
    )
    (net (code "56") (name "/OLDI0_A0_P") (class "Default")
      (node (ref "R303") (pin "1") (pinfunction "1_1") (pintype "passive"))
      (node (ref "U301") (pin "10") (pinfunction "A0P_10") (pintype "passive"))
    )
    (net (code "57") (name "/OLDI0_A1_N") (class "Default")
      (node (ref "R304") (pin "2") (pinfunction "2_2") (pintype "passive"))
      (node (ref "U301") (pin "11") (pinfunction "A1M_11") (pintype "passive"))
    )
    (net (code "58") (name "/OLDI0_A1_P") (class "Default")
      (node (ref "R304") (pin "1") (pinfunction "1_1") (pintype "passive"))
      (node (ref "U301") (pin "12") (pinfunction "A1P_12") (pintype "passive"))
    )
    (net (code "59") (name "/OLDI0_A2_N") (class "Default")
      (node (ref "R305") (pin "2") (pinfunction "2_2") (pintype "passive"))
      (node (ref "U301") (pin "15") (pinfunction "A2M_15") (pintype "passive"))
    )
    (net (code "60") (name "/OLDI0_A2_P") (class "Default")
      (node (ref "R305") (pin "1") (pinfunction "1_1") (pintype "passive"))
      (node (ref "U301") (pin "16") (pinfunction "A2P_16") (pintype "passive"))
    )
    (net (code "61") (name "/OLDI0_A3_N") (class "Default")
      (node (ref "R306") (pin "2") (pinfunction "2_2") (pintype "passive"))
      (node (ref "U301") (pin "19") (pinfunction "A3M_19") (pintype "passive"))
    )
    (net (code "62") (name "/OLDI0_A3_P") (class "Default")
      (node (ref "R306") (pin "1") (pinfunction "1_1") (pintype "passive"))
      (node (ref "U301") (pin "20") (pinfunction "A3P_20") (pintype "passive"))
    )
    (net (code "63") (name "/OLDI0_CLK1_N") (class "Default")
      (node (ref "R301") (pin "1") (pinfunction "1_1") (pintype "passive"))
      (node (ref "U301") (pin "17") (pinfunction "CLKINM_17") (pintype "passive"))
    )
    (net (code "64") (name "/OLDI0_CLK1_P") (class "Default")
      (node (ref "R301") (pin "2") (pinfunction "2_2") (pintype "passive"))
      (node (ref "U301") (pin "18") (pinfunction "CLKINP_18") (pintype "passive"))
    )
    (net (code "65") (name "/OLDI_RESETn") (class "Default")
      (node (ref "D303") (pin "2") (pinfunction "C_2") (pintype "passive"))
    )
    (net (code "66") (name "/PORz_OUT") (class "Default")
      (node (ref "D304") (pin "2") (pinfunction "C_2") (pintype "passive"))
    )
    (net (code "67") (name "/RESETSTATz") (class "Default")
      (node (ref "D305") (pin "2") (pinfunction "C_2") (pintype "passive"))
    )
    (net (code "68") (name "/RESETn") (class "Default")
      (node (ref "C327") (pin "1") (pinfunction "1_1") (pintype "passive"))
      (node (ref "D303") (pin "1") (pinfunction "A_1") (pintype "passive"))
      (node (ref "D304") (pin "1") (pinfunction "A_1") (pintype "passive"))
      (node (ref "D305") (pin "1") (pinfunction "A_1") (pintype "passive"))
      (node (ref "R314") (pin "1") (pinfunction "1_1") (pintype "passive"))
      (node (ref "U302") (pin "51") (pinfunction "RESET#_51") (pintype "passive"))
    )
    (net (code "69") (name "/SHTDN_OLDI") (class "Default")
      (node (ref "R302") (pin "1") (pinfunction "1_1") (pintype "passive"))
      (node (ref "U301") (pin "25") (pinfunction "~{SHTDN}_25") (pintype "passive"))
    )
    (net (code "70") (name "/SWING") (class "Default")
      (node (ref "R312") (pin "1") (pinfunction "1_1") (pintype "passive"))
      (node (ref "U302") (pin "56") (pinfunction "EXT_SWING_56") (pintype "passive"))
    )
    (net (code "71") (name "/TX0_N") (class "Default")
      (node (ref "L303") (pin "4") (pinfunction "4_4") (pintype "passive"))
      (node (ref "U302") (pin "61") (pinfunction "TX0M_61") (pintype "passive"))
    )
    (net (code "72") (name "/TX0_P") (class "Default")
      (node (ref "L303") (pin "1") (pinfunction "1_1") (pintype "passive"))
      (node (ref "U302") (pin "62") (pinfunction "TX0P_62") (pintype "passive"))
    )
    (net (code "73") (name "/TX1_N") (class "Default")
      (node (ref "L302") (pin "4") (pinfunction "4_4") (pintype "passive"))
      (node (ref "U302") (pin "64") (pinfunction "TX1M_64") (pintype "passive"))
    )
    (net (code "74") (name "/TX1_P") (class "Default")
      (node (ref "L302") (pin "1") (pinfunction "1_1") (pintype "passive"))
      (node (ref "U302") (pin "65") (pinfunction "TX1P_65") (pintype "passive"))
    )
    (net (code "75") (name "/TX2_N") (class "Default")
      (node (ref "L301") (pin "4") (pinfunction "4_4") (pintype "passive"))
      (node (ref "U302") (pin "67") (pinfunction "TX2M_67") (pintype "passive"))
    )
    (net (code "76") (name "/TX2_P") (class "Default")
      (node (ref "L301") (pin "1") (pinfunction "1_1") (pintype "passive"))
      (node (ref "U302") (pin "68") (pinfunction "TX2P_68") (pintype "passive"))
    )
    (net (code "77") (name "/TXC_N") (class "Default")
      (node (ref "L304") (pin "4") (pinfunction "4_4") (pintype "passive"))
      (node (ref "U302") (pin "58") (pinfunction "TXCM_58") (pintype "passive"))
    )
    (net (code "78") (name "/TXC_P") (class "Default")
      (node (ref "L304") (pin "1") (pinfunction "1_1") (pintype "passive"))
      (node (ref "U302") (pin "59") (pinfunction "TXCP_59") (pintype "passive"))
    )
    (net (code "79") (name "GND") (class "Default")
      (node (ref "C301") (pin "2") (pinfunction "2_2") (pintype "passive"))
      (node (ref "C302") (pin "2") (pinfunction "2_2") (pintype "passive"))
      (node (ref "C303") (pin "2") (pinfunction "2_2") (pintype "passive"))
      (node (ref "C304") (pin "2") (pinfunction "2_2") (pintype "passive"))
      (node (ref "C305") (pin "2") (pinfunction "2_2") (pintype "passive"))
      (node (ref "C306") (pin "2") (pinfunction "2_2") (pintype "passive"))
      (node (ref "C307") (pin "2") (pinfunction "2_2") (pintype "passive"))
      (node (ref "C308") (pin "2") (pinfunction "2_2") (pintype "passive"))
      (node (ref "C309") (pin "2") (pinfunction "2_2") (pintype "passive"))
      (node (ref "C310") (pin "2") (pinfunction "2_2") (pintype "passive"))
      (node (ref "C311") (pin "2") (pinfunction "2_2") (pintype "passive"))
      (node (ref "C312") (pin "2") (pinfunction "2_2") (pintype "passive"))
      (node (ref "C313") (pin "2") (pinfunction "2_2") (pintype "passive"))
      (node (ref "C314") (pin "2") (pinfunction "2_2") (pintype "passive"))
      (node (ref "C315") (pin "2") (pinfunction "2_2") (pintype "passive"))
      (node (ref "C316") (pin "2") (pinfunction "2_2") (pintype "passive"))
      (node (ref "C317") (pin "2") (pinfunction "2_2") (pintype "passive"))
      (node (ref "C318") (pin "2") (pinfunction "2_2") (pintype "passive"))
      (node (ref "C319") (pin "2") (pinfunction "2_2") (pintype "passive"))
      (node (ref "C320") (pin "2") (pinfunction "2_2") (pintype "passive"))
      (node (ref "C321") (pin "2") (pinfunction "2_2") (pintype "passive"))
      (node (ref "C322") (pin "2") (pinfunction "2_2") (pintype "passive"))
      (node (ref "C323") (pin "2") (pinfunction "2_2") (pintype "passive"))
      (node (ref "C324") (pin "2") (pinfunction "2_2") (pintype "passive"))
      (node (ref "C325") (pin "2") (pinfunction "2_2") (pintype "passive"))
      (node (ref "C326") (pin "2") (pinfunction "2_2") (pintype "passive"))
      (node (ref "C327") (pin "2") (pinfunction "2_2") (pintype "passive"))
      (node (ref "D302") (pin "3") (pinfunction "GND1_3") (pintype "passive"))
      (node (ref "D302") (pin "8") (pinfunction "GND1_8") (pintype "passive"))
      (node (ref "J301") (pin "11") (pinfunction "CKGND_11") (pintype "power_in"))
      (node (ref "J301") (pin "17") (pinfunction "DDCGND_17") (pintype "power_in"))
      (node (ref "J301") (pin "2") (pinfunction "D2GND_2") (pintype "power_in"))
      (node (ref "J301") (pin "20") (pinfunction "GND1_20") (pintype "passive"))
      (node (ref "J301") (pin "21") (pinfunction "GND2_21") (pintype "passive"))
      (node (ref "J301") (pin "22") (pinfunction "GND3_22") (pintype "passive"))
      (node (ref "J301") (pin "23") (pinfunction "GND4_23") (pintype "passive"))
      (node (ref "J301") (pin "5") (pinfunction "D1GND_5") (pintype "power_in"))
      (node (ref "J301") (pin "8") (pinfunction "D0GND_8") (pintype "power_in"))
      (node (ref "R310") (pin "1") (pinfunction "1_1") (pintype "passive"))
      (node (ref "R312") (pin "2") (pinfunction "2_2") (pintype "passive"))
      (node (ref "R313") (pin "1") (pinfunction "1_1") (pintype "passive"))
      (node (ref "U301") (pin "14") (pinfunction "LVDSGND_14") (pintype "passive"))
      (node (ref "U301") (pin "21") (pinfunction "LVDSGND_2_21") (pintype "passive"))
      (node (ref "U301") (pin "22") (pinfunction "PLLGND_2_22") (pintype "passive"))
      (node (ref "U301") (pin "24") (pinfunction "PLLGND_24") (pintype "passive"))
      (node (ref "U301") (pin "28") (pinfunction "GND_4_28") (pintype "passive"))
      (node (ref "U301") (pin "36") (pinfunction "GND_36") (pintype "passive"))
      (node (ref "U301") (pin "4") (pinfunction "GND_5_4") (pintype "passive"))
      (node (ref "U301") (pin "44") (pinfunction "GND_2_44") (pintype "passive"))
      (node (ref "U301") (pin "52") (pinfunction "GND_3_52") (pintype "passive"))
      (node (ref "U301") (pin "8") (pinfunction "LVDSGND_3_8") (pintype "passive"))
      (node (ref "U302") (pin "43") (pinfunction "CGND_43") (pintype "passive"))
      (node (ref "U302") (pin "55") (pinfunction "RSVDL_55") (pintype "passive"))
      (node (ref "U302") (pin "57") (pinfunction "IOGND_57") (pintype "passive"))
      (node (ref "U302") (pin "63") (pinfunction "AGND_63") (pintype "passive"))
      (node (ref "U302") (pin "69") (pinfunction "IO_SEL_69") (pintype "passive"))
      (node (ref "U302") (pin "70") (pinfunction "VDDQ_70") (pintype "passive"))
      (node (ref "U302") (pin "73") (pinfunction "PAD_73") (pintype "passive"))
    )
    (net (code "80") (name "Net-(D301-C)") (class "Default")
      (node (ref "D301") (pin "2") (pinfunction "C_2") (pintype "passive"))
      (node (ref "F301") (pin "1") (pinfunction "1_1") (pintype "passive"))
    )
    (net (code "81") (name "Net-(U302-CI2CA)") (class "Default")
      (node (ref "R309") (pin "1") (pinfunction "1_1") (pintype "passive"))
      (node (ref "U302") (pin "72") (pinfunction "CI2CA_72") (pintype "passive"))
    )
    (net (code "82") (name "Net-(U302-SPDIF)") (class "Default")
      (node (ref "R313") (pin "2") (pinfunction "2_2") (pintype "passive"))
      (node (ref "U302") (pin "36") (pinfunction "SPDIF_36") (pintype "passive"))
    )
    (net (code "83") (name "unconnected-(J301-Utility-Pad14)") (class "Default")
      (node (ref "J301") (pin "14") (pinfunction "Utility_14") (pintype "passive+no_connect"))
    )
    (net (code "84") (name "unconnected-(U302-CEC_D-Pad50)") (class "Default")
      (node (ref "U302") (pin "50") (pinfunction "CEC_D_50") (pintype "passive+no_connect"))
    )
    (net (code "85") (name "unconnected-(U302-MCLK-Pad38)") (class "Default")
      (node (ref "U302") (pin "38") (pinfunction "MCLK_38") (pintype "passive+no_connect"))
    )
    (net (code "86") (name "unconnected-(U302-SCK-Pad45)") (class "Default")
      (node (ref "U302") (pin "45") (pinfunction "SCK_45") (pintype "passive+no_connect"))
    )
    (net (code "87") (name "unconnected-(U302-SD1-Pad40)") (class "Default")
      (node (ref "U302") (pin "40") (pinfunction "SD1_40") (pintype "passive+no_connect"))
    )
    (net (code "88") (name "unconnected-(U302-SD2-Pad39)") (class "Default")
      (node (ref "U302") (pin "39") (pinfunction "SD2_39") (pintype "passive+no_connect"))
    )
    (net (code "89") (name "unconnected-(U302-SD3-Pad37)") (class "Default")
      (node (ref "U302") (pin "37") (pinfunction "SD3_37") (pintype "passive+no_connect"))
    )
    (net (code "90") (name "unconnected-(U302-SDO-Pad41)") (class "Default")
      (node (ref "U302") (pin "41") (pinfunction "SDO_41") (pintype "passive+no_connect"))
    )
    (net (code "91") (name "unconnected-(U302-WS-Pad44)") (class "Default")
      (node (ref "U302") (pin "44") (pinfunction "WS_44") (pintype "passive+no_connect"))
    )
  )
)
